# Neuralynx_EIB16.net
KiCad netlist of a schematic drawn in EAGLE
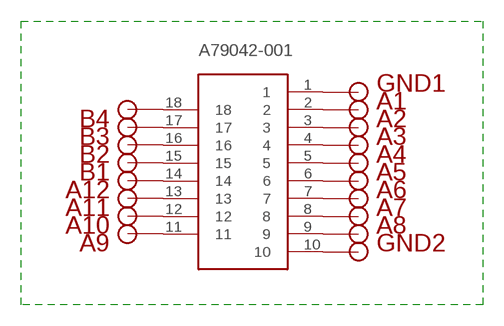
[diagram p0: schematic, sheet 1]

(export (version "E")
  (design (tool "Eeschema 10.0.6"))
  (components
    (comp (ref "A1")
      (value "VIA_20MILL")
      (footprint "eagle-import:VIA_20MIL")
      (libsource (lib "eagle-import") (part "VIA_20MILL"))
    )
    (comp (ref "A2")
      (value "VIA_20MILL")
      (footprint "eagle-import:VIA_20MIL")
      (libsource (lib "eagle-import") (part "VIA_20MILL"))
    )
    (comp (ref "A3")
      (value "VIA_20MILL")
      (footprint "eagle-import:VIA_20MIL")
      (libsource (lib "eagle-import") (part "VIA_20MILL"))
    )
    (comp (ref "A4")
      (value "VIA_20MILL")
      (footprint "eagle-import:VIA_20MIL")
      (libsource (lib "eagle-import") (part "VIA_20MILL"))
    )
    (comp (ref "A5")
      (value "VIA_20MILL")
      (footprint "eagle-import:VIA_20MIL")
      (libsource (lib "eagle-import") (part "VIA_20MILL"))
    )
    (comp (ref "A6")
      (value "VIA_20MILL")
      (footprint "eagle-import:VIA_20MIL")
      (libsource (lib "eagle-import") (part "VIA_20MILL"))
    )
    (comp (ref "A7")
      (value "VIA_20MILL")
      (footprint "eagle-import:VIA_20MIL")
      (libsource (lib "eagle-import") (part "VIA_20MILL"))
    )
    (comp (ref "A8")
      (value "VIA_20MILL")
      (footprint "eagle-import:VIA_20MIL")
      (libsource (lib "eagle-import") (part "VIA_20MILL"))
    )
    (comp (ref "A9")
      (value "VIA_20MILL")
      (footprint "eagle-import:VIA_20MIL")
      (libsource (lib "eagle-import") (part "VIA_20MILL"))
    )
    (comp (ref "A10")
      (value "VIA_20MILL")
      (footprint "eagle-import:VIA_20MIL")
      (libsource (lib "eagle-import") (part "VIA_20MILL"))
    )
    (comp (ref "A11")
      (value "VIA_20MILL")
      (footprint "eagle-import:VIA_20MIL")
      (libsource (lib "eagle-import") (part "VIA_20MILL"))
    )
    (comp (ref "A12")
      (value "VIA_20MILL")
      (footprint "eagle-import:VIA_20MIL")
      (libsource (lib "eagle-import") (part "VIA_20MILL"))
    )
    (comp (ref "A79042-001")
      (value "A79043-001")
      (footprint "eagle-import:OMNETCS-18PIN-SMD")
      (libsource (lib "eagle-import") (part "A79043-001"))
    )
    (comp (ref "B1")
      (value "VIA_20MILL")
      (footprint "eagle-import:VIA_20MIL")
      (libsource (lib "eagle-import") (part "VIA_20MILL"))
    )
    (comp (ref "B2")
      (value "VIA_20MILL")
      (footprint "eagle-import:VIA_20MIL")
      (libsource (lib "eagle-import") (part "VIA_20MILL"))
    )
    (comp (ref "B3")
      (value "VIA_20MILL")
      (footprint "eagle-import:VIA_20MIL")
      (libsource (lib "eagle-import") (part "VIA_20MILL"))
    )
    (comp (ref "B4")
      (value "VIA_20MILL")
      (footprint "eagle-import:VIA_20MIL")
      (libsource (lib "eagle-import") (part "VIA_20MILL"))
    )
    (comp (ref "GND1")
      (value "VIA_20MILL")
      (footprint "eagle-import:VIA_20MIL")
      (libsource (lib "eagle-import") (part "VIA_20MILL"))
    )
    (comp (ref "GND2")
      (value "VIA_20MILL")
      (footprint "eagle-import:VIA_20MIL")
      (libsource (lib "eagle-import") (part "VIA_20MILL"))
    )
  )
  (nets
    (net (code "1") (name "Net-(A1-1)") (class "Default")
      (node (ref "A1") (pin "P$1") (pinfunction "1_P$1") (pintype "bidirectional"))
      (node (ref "A79042-001") (pin "2") (pinfunction "2_2") (pintype "bidirectional"))
    )
    (net (code "2") (name "Net-(A2-1)") (class "Default")
      (node (ref "A2") (pin "P$1") (pinfunction "1_P$1") (pintype "bidirectional"))
      (node (ref "A79042-001") (pin "3") (pinfunction "3_3") (pintype "bidirectional"))
    )
    (net (code "3") (name "Net-(A3-1)") (class "Default")
      (node (ref "A3") (pin "P$1") (pinfunction "1_P$1") (pintype "bidirectional"))
      (node (ref "A79042-001") (pin "4") (pinfunction "4_4") (pintype "bidirectional"))
    )
    (net (code "4") (name "Net-(A4-1)") (class "Default")
      (node (ref "A4") (pin "P$1") (pinfunction "1_P$1") (pintype "bidirectional"))
      (node (ref "A79042-001") (pin "5") (pinfunction "5_5") (pintype "bidirectional"))
    )
    (net (code "5") (name "Net-(A5-1)") (class "Default")
      (node (ref "A5") (pin "P$1") (pinfunction "1_P$1") (pintype "bidirectional"))
      (node (ref "A79042-001") (pin "6") (pinfunction "6_6") (pintype "bidirectional"))
    )
    (net (code "6") (name "Net-(A6-1)") (class "Default")
      (node (ref "A6") (pin "P$1") (pinfunction "1_P$1") (pintype "bidirectional"))
      (node (ref "A79042-001") (pin "7") (pinfunction "7_7") (pintype "bidirectional"))
    )
    (net (code "7") (name "Net-(A7-1)") (class "Default")
      (node (ref "A7") (pin "P$1") (pinfunction "1_P$1") (pintype "bidirectional"))
      (node (ref "A79042-001") (pin "8") (pinfunction "8_8") (pintype "bidirectional"))
    )
    (net (code "8") (name "Net-(A8-1)") (class "Default")
      (node (ref "A79042-001") (pin "9") (pinfunction "9_9") (pintype "bidirectional"))
      (node (ref "A8") (pin "P$1") (pinfunction "1_P$1") (pintype "bidirectional"))
    )
    (net (code "9") (name "Net-(A9-1)") (class "Default")
      (node (ref "A79042-001") (pin "11") (pinfunction "11_11") (pintype "bidirectional"))
      (node (ref "A9") (pin "P$1") (pinfunction "1_P$1") (pintype "bidirectional"))
    )
    (net (code "10") (name "Net-(A10-1)") (class "Default")
      (node (ref "A10") (pin "P$1") (pinfunction "1_P$1") (pintype "bidirectional"))
      (node (ref "A79042-001") (pin "12") (pinfunction "12_12") (pintype "bidirectional"))
    )
    (net (code "11") (name "Net-(A11-1)") (class "Default")
      (node (ref "A11") (pin "P$1") (pinfunction "1_P$1") (pintype "bidirectional"))
      (node (ref "A79042-001") (pin "13") (pinfunction "13_13") (pintype "bidirectional"))
    )
    (net (code "12") (name "Net-(A12-1)") (class "Default")
      (node (ref "A12") (pin "P$1") (pinfunction "1_P$1") (pintype "bidirectional"))
      (node (ref "A79042-001") (pin "14") (pinfunction "14_14") (pintype "bidirectional"))
    )
    (net (code "13") (name "Net-(B1-1)") (class "Default")
      (node (ref "A79042-001") (pin "15") (pinfunction "15_15") (pintype "bidirectional"))
      (node (ref "B1") (pin "P$1") (pinfunction "1_P$1") (pintype "bidirectional"))
    )
    (net (code "14") (name "Net-(B2-1)") (class "Default")
      (node (ref "A79042-001") (pin "16") (pinfunction "16_16") (pintype "bidirectional"))
      (node (ref "B2") (pin "P$1") (pinfunction "1_P$1") (pintype "bidirectional"))
    )
    (net (code "15") (name "Net-(B3-1)") (class "Default")
      (node (ref "A79042-001") (pin "17") (pinfunction "17_17") (pintype "bidirectional"))
      (node (ref "B3") (pin "P$1") (pinfunction "1_P$1") (pintype "bidirectional"))
    )
    (net (code "16") (name "Net-(B4-1)") (class "Default")
      (node (ref "A79042-001") (pin "18") (pinfunction "18_18") (pintype "bidirectional"))
      (node (ref "B4") (pin "P$1") (pinfunction "1_P$1") (pintype "bidirectional"))
    )
    (net (code "17") (name "Net-(GND1-1)") (class "Default")
      (node (ref "A79042-001") (pin "1") (pinfunction "1_1") (pintype "bidirectional"))
      (node (ref "GND1") (pin "P$1") (pinfunction "1_P$1") (pintype "bidirectional"))
    )
    (net (code "18") (name "Net-(GND2-1)") (class "Default")
      (node (ref "A79042-001") (pin "10") (pinfunction "10_10") (pintype "bidirectional"))
      (node (ref "GND2") (pin "P$1") (pinfunction "1_P$1") (pintype "bidirectional"))
    )
  )
)
